# Sheet2.net
KiCad netlist of a schematic drawn in Altium Designer
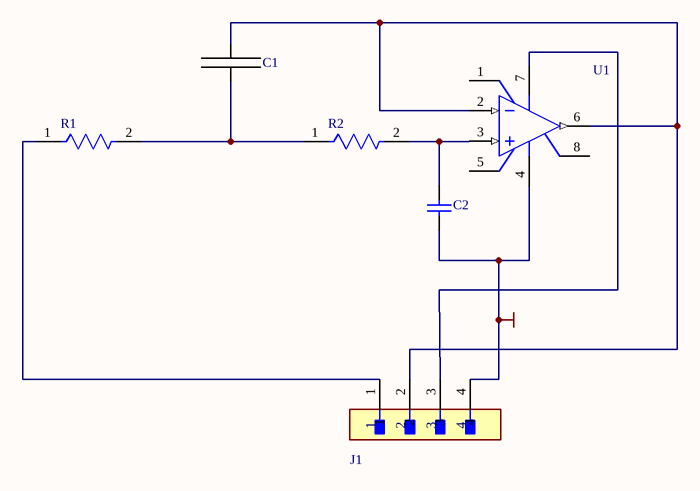
[diagram p0: Sheet2.SchDoc]

(export (version "E")
  (design (tool "Eeschema 10.0.6"))
  (components
    (comp (ref "C1") (value "Cap_0805") (footprint "C_0805") (libsource (lib "Cap") (part "Cap_0805")))
    (comp (ref "C2")
      (value "06035A160JAT2A")
      (footprint "CAPC1608X90X35ML15T15")
      (fields (field (name "MANUFACTURER") "AVX Interconnect / Elco"))
      (libsource (lib "Altium Content Vault") (part "CAP"))
    )
    (comp (ref "J1")
      (value "DF3A-4P-2DSA")
      (footprint "FP-DF3A-4P-2DSA-MFG")
      (description "CONN HEADER VERT 4POS 2MM")
      (libsource (lib "Altium Content Vault") (part "299a8cea1bdcbc3624fe62c390fa72c"))
    )
    (comp (ref "R1")
      (value "RG1005P-393-B-T5")
      (footprint "FP-RG1005-IPC_B")
      (description "Automotive Metal Thin Film Chip Resistor, 0402, 39kΩ, 0.1%, 25ppm/°C, 0.0625W, 75V")
      (fields (field (name "TOLERANCE") "0.1%"))
      (libsource (lib "Altium Content Vault") (part "1029c3af85768c4190bb7ad29bc67b5"))
    )
    (comp (ref "R2")
      (value "RG1005P-393-B-T5")
      (footprint "FP-RG1005-IPC_B")
      (description "Automotive Metal Thin Film Chip Resistor, 0402, 39kΩ, 0.1%, 25ppm/°C, 0.0625W, 75V")
      (fields (field (name "TOLERANCE") "0.1%"))
      (libsource (lib "Altium Content Vault") (part "1029c3af85768c4190bb7ad29bc67b5"))
    )
    (comp (ref "U1")
      (value "LM741H")
      (footprint "LMC0008A")
      (description "Operational Amplifier, 8-pin TO-99")
      (fields (field (name "MANUFACTURER") "Texas Instruments"))
      (libsource (lib "Altium Content Vault") (part "AMP-OPA-LM741-8"))
    )
  )
  (nets
    (net (code "1") (name "<NO NET>") (class "Default")
      (node (ref "C2") (pin "1") (pinfunction "1_1") (pintype "passive"))
      (node (ref "J1") (pin "4") (pinfunction "4_4") (pintype "passive"))
      (node (ref "U1") (pin "4") (pinfunction "V-_4") (pintype "power_in"))
    )
    (net (code "2") (name "Net-(C1-Pad1)") (class "Default")
      (node (ref "C1") (pin "1") (pinfunction "1_1") (pintype "passive"))
      (node (ref "R1") (pin "2") (pinfunction "2_2") (pintype "passive"))
      (node (ref "R2") (pin "1") (pinfunction "1_1") (pintype "passive"))
    )
    (net (code "3") (name "Net-(J1-Pad1)") (class "Default")
      (node (ref "J1") (pin "1") (pinfunction "1_1") (pintype "passive"))
      (node (ref "R1") (pin "1") (pinfunction "1_1") (pintype "passive"))
    )
    (net (code "4") (name "Net-(U1-IN+)") (class "Default")
      (node (ref "C2") (pin "2") (pinfunction "2_2") (pintype "passive"))
      (node (ref "R2") (pin "2") (pinfunction "2_2") (pintype "passive"))
      (node (ref "U1") (pin "3") (pinfunction "IN+_3") (pintype "input"))
    )
    (net (code "5") (name "Net-(U1-IN-)") (class "Default")
      (node (ref "C1") (pin "2") (pinfunction "2_2") (pintype "passive"))
      (node (ref "J1") (pin "2") (pinfunction "2_2") (pintype "passive"))
      (node (ref "U1") (pin "2") (pinfunction "IN-_2") (pintype "input"))
      (node (ref "U1") (pin "6") (pinfunction "OUT_6") (pintype "output"))
    )
    (net (code "6") (name "Net-(U1-V+)") (class "Default")
      (node (ref "J1") (pin "3") (pinfunction "3_3") (pintype "passive"))
      (node (ref "U1") (pin "7") (pinfunction "V+_7") (pintype "power_in"))
    )
    (net (code "7") (name "unconnected-(U1-NC-Pad8)") (class "Default")
      (node (ref "U1") (pin "8") (pinfunction "NC_8") (pintype "passive"))
    )
    (net (code "8") (name "unconnected-(U1-OFS_NULL-Pad1)") (class "Default")
      (node (ref "U1") (pin "1") (pinfunction "OFS_NULL_1") (pintype "passive"))
    )
    (net (code "9") (name "unconnected-(U1-OFS_NULL-Pad5)") (class "Default")
      (node (ref "U1") (pin "5") (pinfunction "OFS_NULL_5") (pintype "passive"))
    )
  )
)
